# audio_spectrum.net
KiCad netlist of a schematic drawn in EAGLE
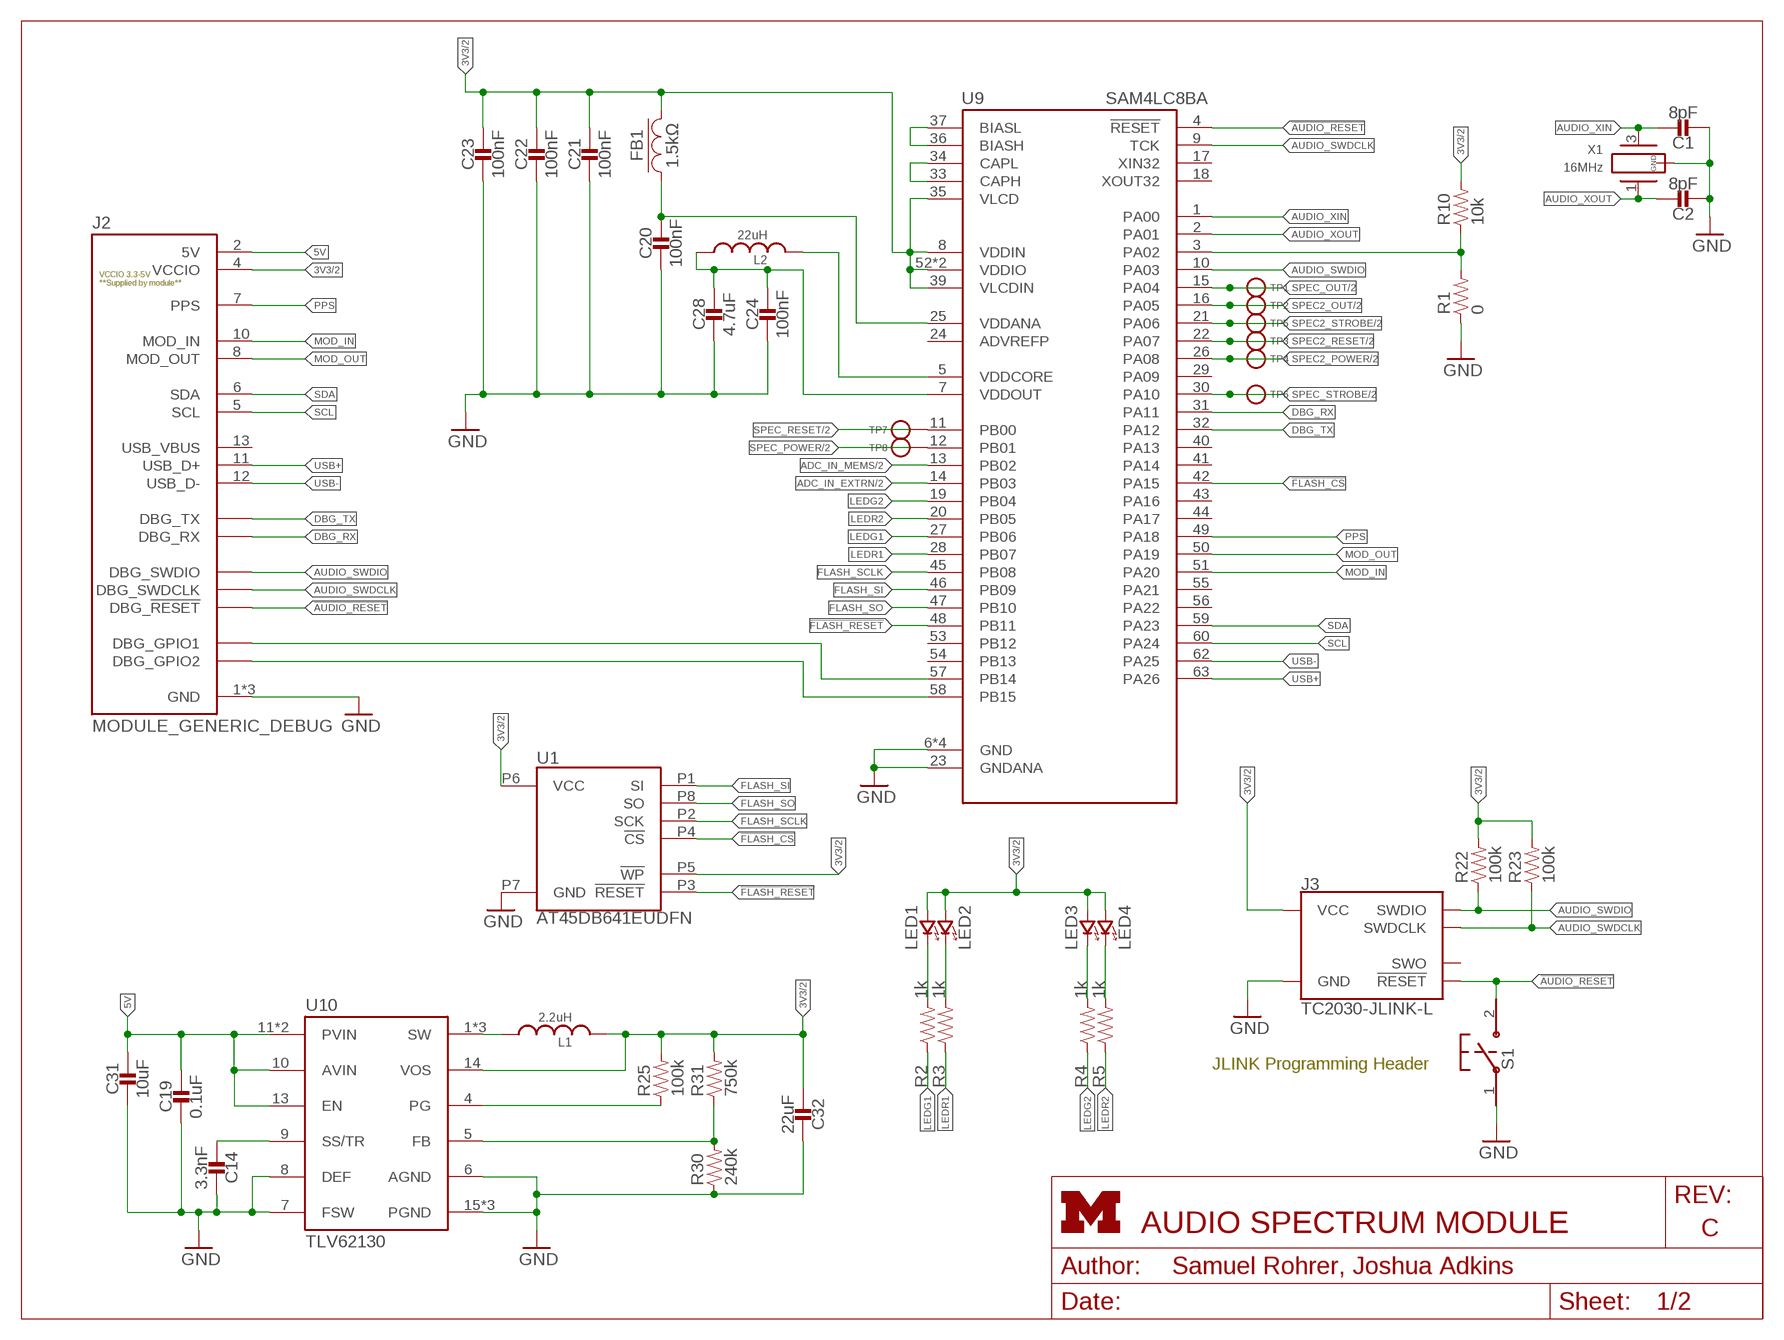
[diagram p0: schematic, sheet 1]
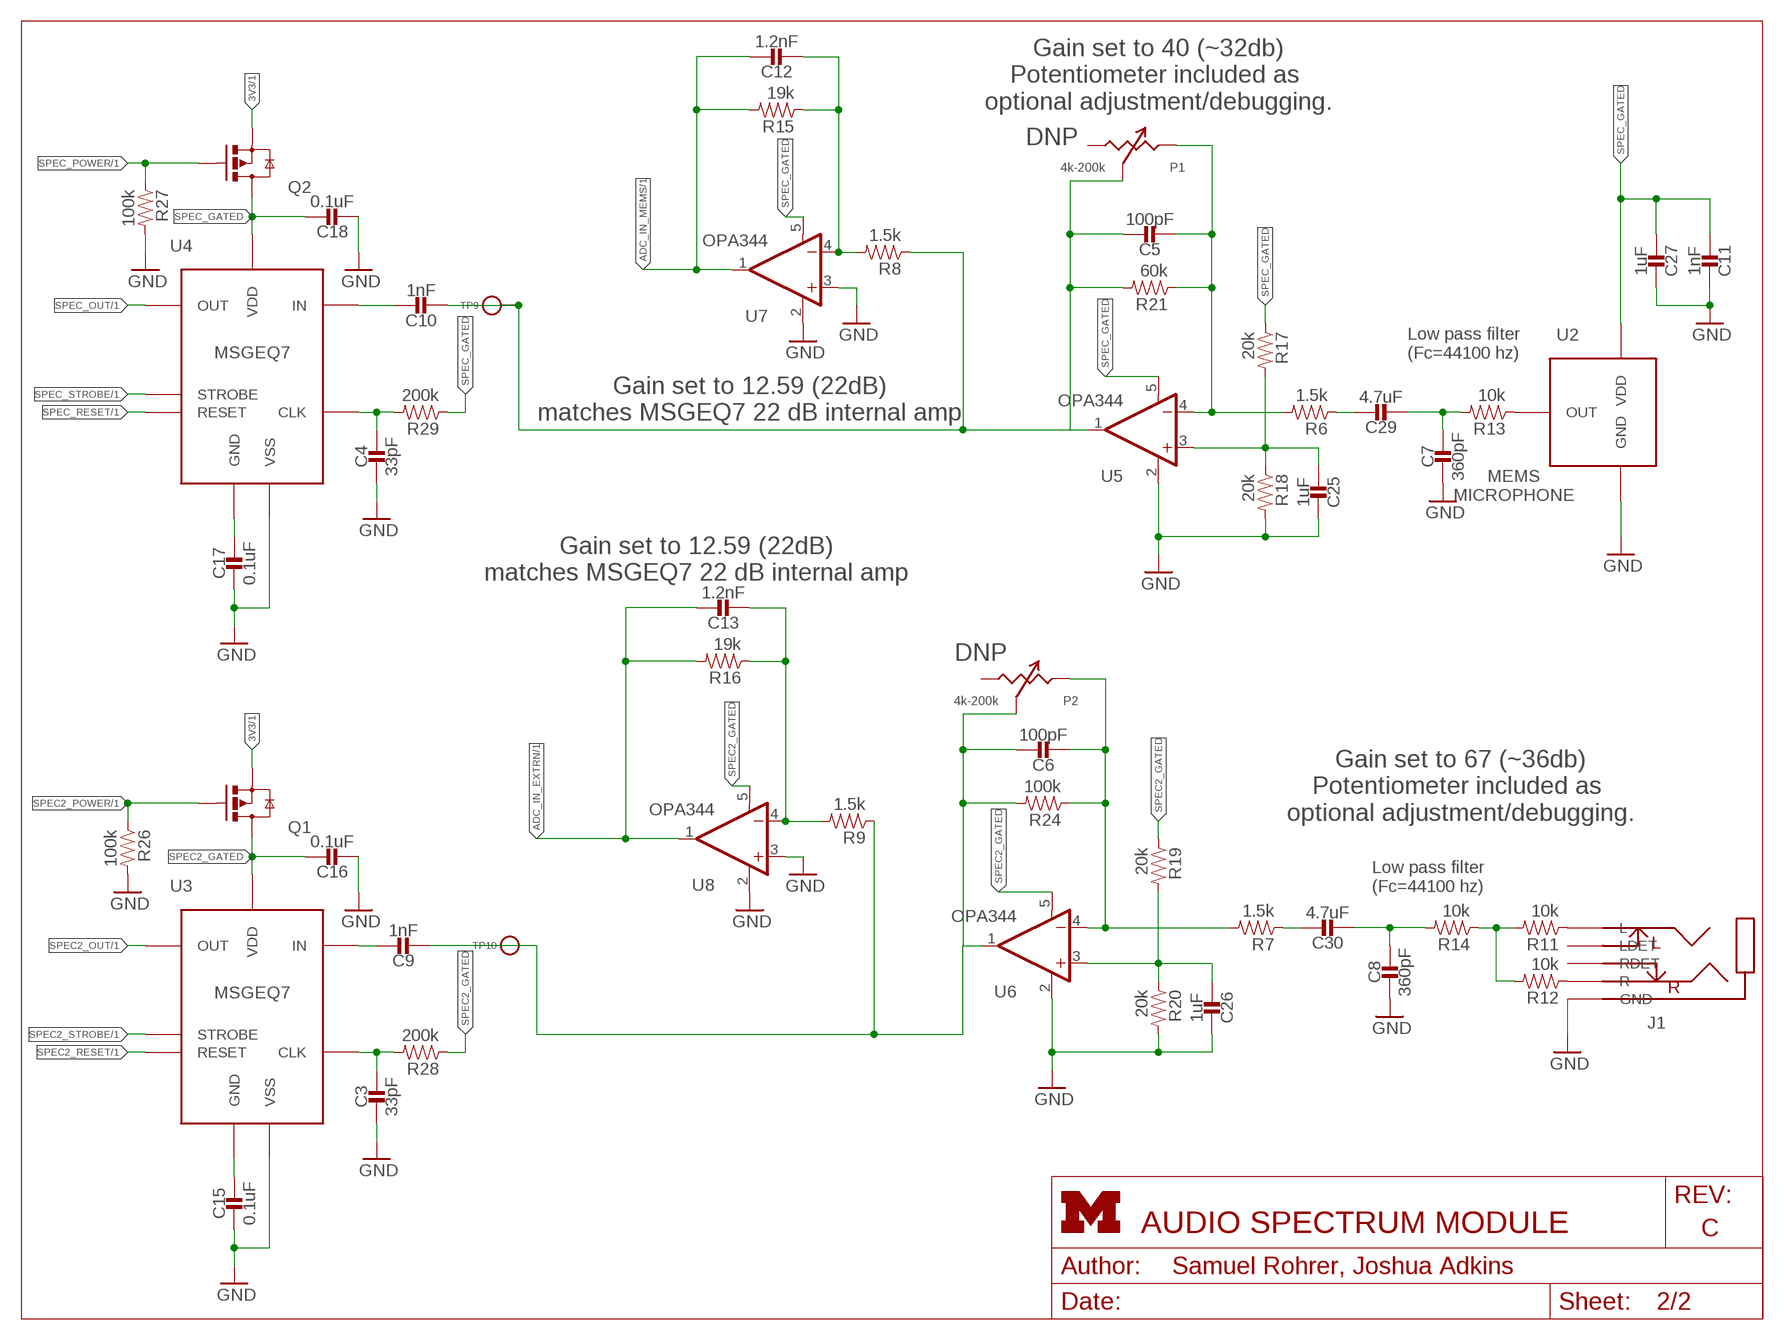
[diagram p1: schematic, sheet 2]

(export (version "E")
  (design (tool "Eeschema 10.0.6"))
  (components
    (comp (ref "C1")
      (value "8pF")
      (footprint "eagle-import:0603_CAP")
      (libsource (lib "eagle-import") (part "CAPACITOR0603_CAP"))
    )
    (comp (ref "C2")
      (value "8pF")
      (footprint "eagle-import:0603_CAP")
      (libsource (lib "eagle-import") (part "CAPACITOR0603_CAP"))
    )
    (comp (ref "C14")
      (value "3.3nF")
      (footprint "eagle-import:0603_CAP")
      (libsource (lib "eagle-import") (part "CAPACITOR0603_CAP"))
    )
    (comp (ref "C19")
      (value "0.1uF")
      (footprint "eagle-import:0603_CAP")
      (libsource (lib "eagle-import") (part "CAPACITOR0603_CAP"))
    )
    (comp (ref "C20")
      (value "100nF")
      (footprint "eagle-import:0603_CAP")
      (libsource (lib "eagle-import") (part "CAPACITOR0603_CAP"))
    )
    (comp (ref "C21")
      (value "100nF")
      (footprint "eagle-import:0603_CAP")
      (libsource (lib "eagle-import") (part "CAPACITOR0603_CAP"))
    )
    (comp (ref "C22")
      (value "100nF")
      (footprint "eagle-import:0603_CAP")
      (libsource (lib "eagle-import") (part "CAPACITOR0603_CAP"))
    )
    (comp (ref "C23")
      (value "100nF")
      (footprint "eagle-import:0603_CAP")
      (libsource (lib "eagle-import") (part "CAPACITOR0603_CAP"))
    )
    (comp (ref "C24")
      (value "100nF")
      (footprint "eagle-import:0402_CAP")
      (libsource (lib "eagle-import") (part "CAPACITOR0402_CAP"))
    )
    (comp (ref "C28")
      (value "4.7uF")
      (footprint "eagle-import:0402_CAP")
      (libsource (lib "eagle-import") (part "CAPACITOR0402_CAP"))
    )
    (comp (ref "C31")
      (value "10uF")
      (footprint "eagle-import:0603_CAP")
      (libsource (lib "eagle-import") (part "CAPACITOR0603_CAP"))
    )
    (comp (ref "C32")
      (value "22uF")
      (footprint "eagle-import:0603_CAP")
      (libsource (lib "eagle-import") (part "CAPACITOR0603_CAP"))
    )
    (comp (ref "FB1")
      (value "1.5kΩ")
      (footprint "eagle-import:0603_CAP")
      (libsource (lib "eagle-import") (part "FERRITE_BEAD0603"))
    )
    (comp (ref "J2")
      (value "MODULE_GENERIC_DEBUG")
      (footprint "eagle-import:MODULE_GENERIC_DEBUG")
      (libsource (lib "eagle-import") (part "MODULE_GENERIC_DEBUG"))
    )
    (comp (ref "J3")
      (value "TC2030-JLINK-L")
      (footprint "eagle-import:TC2030-IDC")
      (libsource (lib "eagle-import") (part "TC2030-JLINK-L"))
    )
    (comp (ref "L1")
      (value "2.2uH")
      (footprint "eagle-import:IHL-1212BZ-11")
      (libsource (lib "eagle-import") (part "INDUCTORIHL"))
    )
    (comp (ref "L2")
      (value "22uH")
      (footprint "eagle-import:1212")
      (libsource (lib "eagle-import") (part "LHQ3NP"))
    )
    (comp (ref "LED1")
      (value "LED0603")
      (footprint "eagle-import:LED-0603")
      (libsource (lib "eagle-import") (part "LED0603"))
    )
    (comp (ref "LED2")
      (value "LED0603")
      (footprint "eagle-import:LED-0603")
      (libsource (lib "eagle-import") (part "LED0603"))
    )
    (comp (ref "LED3")
      (value "LED0603")
      (footprint "eagle-import:LED-0603")
      (libsource (lib "eagle-import") (part "LED0603"))
    )
    (comp (ref "LED4")
      (value "LED0603")
      (footprint "eagle-import:LED-0603")
      (libsource (lib "eagle-import") (part "LED0603"))
    )
    (comp (ref "R1")
      (value "0")
      (footprint "eagle-import:0603-RES")
      (libsource (lib "eagle-import") (part "RESISTOR0603_RES"))
    )
    (comp (ref "R2")
      (value "1k")
      (footprint "eagle-import:0603-RES")
      (libsource (lib "eagle-import") (part "RESISTOR0603_RES"))
    )
    (comp (ref "R3")
      (value "1k")
      (footprint "eagle-import:0603-RES")
      (libsource (lib "eagle-import") (part "RESISTOR0603_RES"))
    )
    (comp (ref "R4")
      (value "1k")
      (footprint "eagle-import:0603-RES")
      (libsource (lib "eagle-import") (part "RESISTOR0603_RES"))
    )
    (comp (ref "R5")
      (value "1k")
      (footprint "eagle-import:0603-RES")
      (libsource (lib "eagle-import") (part "RESISTOR0603_RES"))
    )
    (comp (ref "R10")
      (value "10k")
      (footprint "eagle-import:0603-RES")
      (libsource (lib "eagle-import") (part "RESISTOR0603_RES"))
    )
    (comp (ref "R22")
      (value "100k")
      (footprint "eagle-import:0603-RES")
      (libsource (lib "eagle-import") (part "RESISTOR0603_RES"))
    )
    (comp (ref "R23")
      (value "100k")
      (footprint "eagle-import:0603-RES")
      (libsource (lib "eagle-import") (part "RESISTOR0603_RES"))
    )
    (comp (ref "R25")
      (value "100k")
      (footprint "eagle-import:0603-RES")
      (libsource (lib "eagle-import") (part "RESISTOR0603_RES"))
    )
    (comp (ref "R30")
      (value "240k")
      (footprint "eagle-import:0603-RES")
      (libsource (lib "eagle-import") (part "RESISTOR0603_RES"))
    )
    (comp (ref "R31")
      (value "750k")
      (footprint "eagle-import:0603-RES")
      (libsource (lib "eagle-import") (part "RESISTOR0603_RES"))
    )
    (comp (ref "S1")
      (value "B3U-1000P")
      (footprint "eagle-import:B3U-1000P")
      (libsource (lib "eagle-import") (part "B3U-1000P"))
    )
    (comp (ref "TP1")
      (value "TEST_POINT_0.040IN")
      (footprint "eagle-import:TESTPOINT_0.040IN")
      (libsource (lib "eagle-import") (part "TEST_POINT_0.040IN"))
    )
    (comp (ref "TP2")
      (value "TEST_POINT_0.040IN")
      (footprint "eagle-import:TESTPOINT_0.040IN")
      (libsource (lib "eagle-import") (part "TEST_POINT_0.040IN"))
    )
    (comp (ref "TP3")
      (value "TEST_POINT_0.040IN")
      (footprint "eagle-import:TESTPOINT_0.040IN")
      (libsource (lib "eagle-import") (part "TEST_POINT_0.040IN"))
    )
    (comp (ref "TP4")
      (value "TEST_POINT_0.040IN")
      (footprint "eagle-import:TESTPOINT_0.040IN")
      (libsource (lib "eagle-import") (part "TEST_POINT_0.040IN"))
    )
    (comp (ref "TP5")
      (value "TEST_POINT_0.040IN")
      (footprint "eagle-import:TESTPOINT_0.040IN")
      (libsource (lib "eagle-import") (part "TEST_POINT_0.040IN"))
    )
    (comp (ref "TP6")
      (value "TEST_POINT_0.040IN")
      (footprint "eagle-import:TESTPOINT_0.040IN")
      (libsource (lib "eagle-import") (part "TEST_POINT_0.040IN"))
    )
    (comp (ref "TP7")
      (value "TEST_POINT_0.040IN")
      (footprint "eagle-import:TESTPOINT_0.040IN")
      (libsource (lib "eagle-import") (part "TEST_POINT_0.040IN"))
    )
    (comp (ref "TP8")
      (value "TEST_POINT_0.040IN")
      (footprint "eagle-import:TESTPOINT_0.040IN")
      (libsource (lib "eagle-import") (part "TEST_POINT_0.040IN"))
    )
    (comp (ref "U1")
      (value "AT45DB641EUDFN")
      (footprint "eagle-import:UDFN-8-5MMX6MM")
      (libsource (lib "eagle-import") (part "AT45DB641EUDFN"))
    )
    (comp (ref "U9")
      (value "SAM4LC8BA")
      (footprint "eagle-import:QFN-64-9MM")
      (libsource (lib "eagle-import") (part "SAM4LC8BA"))
    )
    (comp (ref "U10")
      (value "TLV62130")
      (footprint "eagle-import:TQFN-16_3MM")
      (libsource (lib "eagle-import") (part "TLV62130"))
    )
    (comp (ref "X1")
      (value "16MHz")
      (footprint "eagle-import:FHXXX")
      (libsource (lib "eagle-import") (part "FH1600015"))
    )
    (comp (ref "C3")
      (value "33pF")
      (footprint "eagle-import:0603_CAP")
      (libsource (lib "eagle-import") (part "CAPACITOR0603_CAP"))
    )
    (comp (ref "C4")
      (value "33pF")
      (footprint "eagle-import:0603_CAP")
      (libsource (lib "eagle-import") (part "CAPACITOR0603_CAP"))
    )
    (comp (ref "C5")
      (value "100pF")
      (footprint "eagle-import:0603_CAP")
      (libsource (lib "eagle-import") (part "CAPACITOR0603_CAP"))
    )
    (comp (ref "C6")
      (value "100pF")
      (footprint "eagle-import:0603_CAP")
      (libsource (lib "eagle-import") (part "CAPACITOR0603_CAP"))
    )
    (comp (ref "C7")
      (value "360pF")
      (footprint "eagle-import:0603_CAP")
      (libsource (lib "eagle-import") (part "CAPACITOR0603_CAP"))
    )
    (comp (ref "C8")
      (value "360pF")
      (footprint "eagle-import:0603_CAP")
      (libsource (lib "eagle-import") (part "CAPACITOR0603_CAP"))
    )
    (comp (ref "C9")
      (value "1nF")
      (footprint "eagle-import:0603_CAP")
      (libsource (lib "eagle-import") (part "CAPACITOR0603_CAP"))
    )
    (comp (ref "C10")
      (value "1nF")
      (footprint "eagle-import:0603_CAP")
      (libsource (lib "eagle-import") (part "CAPACITOR0603_CAP"))
    )
    (comp (ref "C11")
      (value "1nF")
      (footprint "eagle-import:0603_CAP")
      (libsource (lib "eagle-import") (part "CAPACITOR0603_CAP"))
    )
    (comp (ref "C12")
      (value "1.2nF")
      (footprint "eagle-import:0603_CAP")
      (libsource (lib "eagle-import") (part "CAPACITOR0603_CAP"))
    )
    (comp (ref "C13")
      (value "1.2nF")
      (footprint "eagle-import:0603_CAP")
      (libsource (lib "eagle-import") (part "CAPACITOR0603_CAP"))
    )
    (comp (ref "C15")
      (value "0.1uF")
      (footprint "eagle-import:0603_CAP")
      (libsource (lib "eagle-import") (part "CAPACITOR0603_CAP"))
    )
    (comp (ref "C16")
      (value "0.1uF")
      (footprint "eagle-import:0603_CAP")
      (libsource (lib "eagle-import") (part "CAPACITOR0603_CAP"))
    )
    (comp (ref "C17")
      (value "0.1uF")
      (footprint "eagle-import:0603_CAP")
      (libsource (lib "eagle-import") (part "CAPACITOR0603_CAP"))
    )
    (comp (ref "C18")
      (value "0.1uF")
      (footprint "eagle-import:0603_CAP")
      (libsource (lib "eagle-import") (part "CAPACITOR0603_CAP"))
    )
    (comp (ref "C25")
      (value "1uF")
      (footprint "eagle-import:0603_CAP")
      (libsource (lib "eagle-import") (part "CAPACITOR0603_CAP"))
    )
    (comp (ref "C26")
      (value "1uF")
      (footprint "eagle-import:0603_CAP")
      (libsource (lib "eagle-import") (part "CAPACITOR0603_CAP"))
    )
    (comp (ref "C27")
      (value "1uF")
      (footprint "eagle-import:0603_CAP")
      (libsource (lib "eagle-import") (part "CAPACITOR0603_CAP"))
    )
    (comp (ref "C29")
      (value "4.7uF")
      (footprint "eagle-import:0603_CAP")
      (libsource (lib "eagle-import") (part "CAPACITOR0603_CAP"))
    )
    (comp (ref "C30")
      (value "4.7uF")
      (footprint "eagle-import:0603_CAP")
      (libsource (lib "eagle-import") (part "CAPACITOR0603_CAP"))
    )
    (comp (ref "J1")
      (value "AUDIO-JACK-VERTICAL")
      (footprint "eagle-import:AUDIO-JACK-VERTICAL")
      (libsource (lib "eagle-import") (part "AUDIO-JACK-VERTICAL"))
    )
    (comp (ref "P1")
      (value "4k-200k")
      (footprint "eagle-import:TC33X-2")
      (libsource (lib "eagle-import") (part "POTTC33X"))
    )
    (comp (ref "P2")
      (value "4k-200k")
      (footprint "eagle-import:TC33X-2")
      (libsource (lib "eagle-import") (part "POTTC33X"))
    )
    (comp (ref "Q1")
      (value "NX3008PBK")
      (footprint "eagle-import:SOT23-3")
      (libsource (lib "eagle-import") (part "NX3008PBK"))
    )
    (comp (ref "Q2")
      (value "NX3008PBK")
      (footprint "eagle-import:SOT23-3")
      (libsource (lib "eagle-import") (part "NX3008PBK"))
    )
    (comp (ref "R6")
      (value "1.5k")
      (footprint "eagle-import:0603-RES")
      (libsource (lib "eagle-import") (part "RESISTOR0603_RES"))
    )
    (comp (ref "R7")
      (value "1.5k")
      (footprint "eagle-import:0603-RES")
      (libsource (lib "eagle-import") (part "RESISTOR0603_RES"))
    )
    (comp (ref "R8")
      (value "1.5k")
      (footprint "eagle-import:0603-RES")
      (libsource (lib "eagle-import") (part "RESISTOR0603_RES"))
    )
    (comp (ref "R9")
      (value "1.5k")
      (footprint "eagle-import:0603-RES")
      (libsource (lib "eagle-import") (part "RESISTOR0603_RES"))
    )
    (comp (ref "R11")
      (value "10k")
      (footprint "eagle-import:0603-RES")
      (libsource (lib "eagle-import") (part "RESISTOR0603_RES"))
    )
    (comp (ref "R12")
      (value "10k")
      (footprint "eagle-import:0603-RES")
      (libsource (lib "eagle-import") (part "RESISTOR0603_RES"))
    )
    (comp (ref "R13")
      (value "10k")
      (footprint "eagle-import:0603-RES")
      (libsource (lib "eagle-import") (part "RESISTOR0603_RES"))
    )
    (comp (ref "R14")
      (value "10k")
      (footprint "eagle-import:0603-RES")
      (libsource (lib "eagle-import") (part "RESISTOR0603_RES"))
    )
    (comp (ref "R15")
      (value "19k")
      (footprint "eagle-import:0603-RES")
      (libsource (lib "eagle-import") (part "RESISTOR0603_RES"))
    )
    (comp (ref "R16")
      (value "19k")
      (footprint "eagle-import:0603-RES")
      (libsource (lib "eagle-import") (part "RESISTOR0603_RES"))
    )
    (comp (ref "R17")
      (value "20k")
      (footprint "eagle-import:0603-RES")
      (libsource (lib "eagle-import") (part "RESISTOR0603_RES"))
    )
    (comp (ref "R18")
      (value "20k")
      (footprint "eagle-import:0603-RES")
      (libsource (lib "eagle-import") (part "RESISTOR0603_RES"))
    )
    (comp (ref "R19")
      (value "20k")
      (footprint "eagle-import:0603-RES")
      (libsource (lib "eagle-import") (part "RESISTOR0603_RES"))
    )
    (comp (ref "R20")
      (value "20k")
      (footprint "eagle-import:0603-RES")
      (libsource (lib "eagle-import") (part "RESISTOR0603_RES"))
    )
    (comp (ref "R21")
      (value "60k")
      (footprint "eagle-import:0603-RES")
      (libsource (lib "eagle-import") (part "RESISTOR0603_RES"))
    )
    (comp (ref "R24")
      (value "100k")
      (footprint "eagle-import:0603-RES")
      (libsource (lib "eagle-import") (part "RESISTOR0603_RES"))
    )
    (comp (ref "R26")
      (value "100k")
      (footprint "eagle-import:0603-RES")
      (libsource (lib "eagle-import") (part "RESISTOR0603_RES"))
    )
    (comp (ref "R27")
      (value "100k")
      (footprint "eagle-import:0603-RES")
      (libsource (lib "eagle-import") (part "RESISTOR0603_RES"))
    )
    (comp (ref "R28")
      (value "200k")
      (footprint "eagle-import:0603-RES")
      (libsource (lib "eagle-import") (part "RESISTOR0603_RES"))
    )
    (comp (ref "R29")
      (value "200k")
      (footprint "eagle-import:0603-RES")
      (libsource (lib "eagle-import") (part "RESISTOR0603_RES"))
    )
    (comp (ref "TP9")
      (value "TEST_POINT_0.040IN")
      (footprint "eagle-import:TESTPOINT_0.040IN")
      (libsource (lib "eagle-import") (part "TEST_POINT_0.040IN"))
    )
    (comp (ref "TP10")
      (value "TEST_POINT_0.040IN")
      (footprint "eagle-import:TESTPOINT_0.040IN")
      (libsource (lib "eagle-import") (part "TEST_POINT_0.040IN"))
    )
    (comp (ref "U2")
      (value "MP23AB02B")
      (footprint "eagle-import:MP23AB02B")
      (libsource (lib "eagle-import") (part "MP23AB02B"))
    )
    (comp (ref "U3")
      (value "MSGEQ7")
      (footprint "eagle-import:DIP-8")
      (libsource (lib "eagle-import") (part "MSGEQ7"))
    )
    (comp (ref "U4")
      (value "MSGEQ7")
      (footprint "eagle-import:DIP-8")
      (libsource (lib "eagle-import") (part "MSGEQ7"))
    )
    (comp (ref "U5")
      (value "OPA344")
      (footprint "eagle-import:SOT23-5")
      (libsource (lib "eagle-import") (part "OPA344"))
    )
    (comp (ref "U6")
      (value "OPA344")
      (footprint "eagle-import:SOT23-5")
      (libsource (lib "eagle-import") (part "OPA344"))
    )
    (comp (ref "U7")
      (value "OPA344")
      (footprint "eagle-import:SOT23-5")
      (libsource (lib "eagle-import") (part "OPA344"))
    )
    (comp (ref "U8")
      (value "OPA344")
      (footprint "eagle-import:SOT23-5")
      (libsource (lib "eagle-import") (part "OPA344"))
    )
  )
  (nets
    (net (code "1") (name "3V3") (class "Default")
      (node (ref "C21") (pin "1") (pinfunction "1_1") (pintype "bidirectional"))
      (node (ref "C22") (pin "1") (pinfunction "1_1") (pintype "bidirectional"))
      (node (ref "C23") (pin "1") (pinfunction "1_1") (pintype "bidirectional"))
      (node (ref "C32") (pin "2") (pinfunction "2_2") (pintype "bidirectional"))
      (node (ref "FB1") (pin "2") (pinfunction "P$2_2") (pintype "bidirectional"))
      (node (ref "J2") (pin "4") (pinfunction "VCCIO_4") (pintype "bidirectional"))
      (node (ref "J3") (pin "1") (pinfunction "VCC_1") (pintype "bidirectional"))
      (node (ref "L1") (pin "P$2") (pinfunction "2_P$2") (pintype "bidirectional"))
      (node (ref "LED1") (pin "A") (pinfunction "ANODE_A") (pintype "bidirectional"))
      (node (ref "LED2") (pin "A") (pinfunction "ANODE_A") (pintype "bidirectional"))
      (node (ref "LED3") (pin "A") (pinfunction "ANODE_A") (pintype "bidirectional"))
      (node (ref "LED4") (pin "A") (pinfunction "ANODE_A") (pintype "bidirectional"))
      (node (ref "Q1") (pin "2") (pinfunction "S_2") (pintype "passive"))
      (node (ref "Q2") (pin "2") (pinfunction "S_2") (pintype "passive"))
      (node (ref "R10") (pin "2") (pinfunction "2_2") (pintype "passive"))
      (node (ref "R22") (pin "2") (pinfunction "2_2") (pintype "passive"))
      (node (ref "R23") (pin "2") (pinfunction "2_2") (pintype "passive"))
      (node (ref "R25") (pin "2") (pinfunction "2_2") (pintype "passive"))
      (node (ref "R31") (pin "2") (pinfunction "2_2") (pintype "passive"))
      (node (ref "U1") (pin "P5") (pinfunction "~{WP}_P5") (pintype "bidirectional"))
      (node (ref "U1") (pin "P6") (pinfunction "VCC_P6") (pintype "bidirectional"))
      (node (ref "U10") (pin "14") (pinfunction "VOS_14") (pintype "bidirectional"))
      (node (ref "U9") (pin "35") (pinfunction "VLCD_35") (pintype "bidirectional"))
      (node (ref "U9") (pin "39") (pinfunction "VLCDIN_39") (pintype "power_in"))
      (node (ref "U9") (pin "52") (pinfunction "VDDIO_52") (pintype "power_in"))
      (node (ref "U9") (pin "61") (pinfunction "VDDIO_61") (pintype "power_in"))
      (node (ref "U9") (pin "8") (pinfunction "VDDIN_8") (pintype "power_in"))
    )
    (net (code "2") (name "5V") (class "Default")
      (node (ref "C19") (pin "1") (pinfunction "1_1") (pintype "bidirectional"))
      (node (ref "C31") (pin "1") (pinfunction "1_1") (pintype "bidirectional"))
      (node (ref "J2") (pin "2") (pinfunction "5V_2") (pintype "bidirectional"))
      (node (ref "U10") (pin "10") (pinfunction "AVIN_10") (pintype "bidirectional"))
      (node (ref "U10") (pin "11") (pinfunction "PVIN_11") (pintype "bidirectional"))
      (node (ref "U10") (pin "12") (pinfunction "PVIN_12") (pintype "bidirectional"))
      (node (ref "U10") (pin "13") (pinfunction "EN_13") (pintype "bidirectional"))
    )
    (net (code "3") (name "ADC_IN_EXTRN") (class "Default")
      (node (ref "C13") (pin "1") (pinfunction "1_1") (pintype "bidirectional"))
      (node (ref "R16") (pin "2") (pinfunction "2_2") (pintype "passive"))
      (node (ref "U8") (pin "1") (pinfunction "OUT_1") (pintype "output"))
      (node (ref "U9") (pin "14") (pinfunction "PB03_14") (pintype "bidirectional"))
    )
    (net (code "4") (name "ADC_IN_MEMS") (class "Default")
      (node (ref "C12") (pin "1") (pinfunction "1_1") (pintype "bidirectional"))
      (node (ref "R15") (pin "2") (pinfunction "2_2") (pintype "passive"))
      (node (ref "U7") (pin "1") (pinfunction "OUT_1") (pintype "output"))
      (node (ref "U9") (pin "13") (pinfunction "PB02_13") (pintype "bidirectional"))
    )
    (net (code "5") (name "AUDIO_SWDCLK") (class "Default")
      (node (ref "J2") (pin "21") (pinfunction "DBG_SWDCLK_21") (pintype "bidirectional"))
      (node (ref "J3") (pin "4") (pinfunction "SWDCLK_4") (pintype "bidirectional"))
      (node (ref "R23") (pin "1") (pinfunction "1_1") (pintype "passive"))
      (node (ref "U9") (pin "9") (pinfunction "TCK_9") (pintype "bidirectional"))
    )
    (net (code "6") (name "AUDIO_SWDIO") (class "Default")
      (node (ref "J2") (pin "22") (pinfunction "DBG_SWDIO_22") (pintype "bidirectional"))
      (node (ref "J3") (pin "2") (pinfunction "SWDIO_2") (pintype "bidirectional"))
      (node (ref "R22") (pin "1") (pinfunction "1_1") (pintype "passive"))
      (node (ref "U9") (pin "10") (pinfunction "PA03_10") (pintype "bidirectional"))
    )
    (net (code "7") (name "AUDIO_XIN") (class "Default")
      (node (ref "C1") (pin "1") (pinfunction "1_1") (pintype "bidirectional"))
      (node (ref "U9") (pin "1") (pinfunction "PA00_1") (pintype "bidirectional"))
      (node (ref "X1") (pin "3") (pinfunction "2_3") (pintype "bidirectional"))
    )
    (net (code "8") (name "AUDIO_XOUT") (class "Default")
      (node (ref "C2") (pin "1") (pinfunction "1_1") (pintype "bidirectional"))
      (node (ref "U9") (pin "2") (pinfunction "PA01_2") (pintype "bidirectional"))
      (node (ref "X1") (pin "1") (pinfunction "1_1") (pintype "bidirectional"))
    )
    (net (code "9") (name "DBG_RX") (class "Default")
      (node (ref "J2") (pin "18") (pinfunction "DBG_RX_18") (pintype "bidirectional"))
      (node (ref "U9") (pin "31") (pinfunction "PA11_31") (pintype "bidirectional"))
    )
    (net (code "10") (name "DBG_TX") (class "Default")
      (node (ref "J2") (pin "17") (pinfunction "DBG_TX_17") (pintype "bidirectional"))
      (node (ref "U9") (pin "32") (pinfunction "PA12_32") (pintype "bidirectional"))
    )
    (net (code "11") (name "FLASH_SCLK") (class "Default")
      (node (ref "U1") (pin "P2") (pinfunction "SCK_P2") (pintype "bidirectional"))
      (node (ref "U9") (pin "45") (pinfunction "PB08_45") (pintype "bidirectional"))
    )
    (net (code "12") (name "FLASH_SI") (class "Default")
      (node (ref "U1") (pin "P1") (pinfunction "SI_P1") (pintype "bidirectional"))
      (node (ref "U9") (pin "46") (pinfunction "PB09_46") (pintype "bidirectional"))
    )
    (net (code "13") (name "FLASH_SO") (class "Default")
      (node (ref "U1") (pin "P8") (pinfunction "SO_P8") (pintype "bidirectional"))
      (node (ref "U9") (pin "47") (pinfunction "PB10_47") (pintype "bidirectional"))
    )
    (net (code "14") (name "GND") (class "Default")
      (node (ref "C1") (pin "2") (pinfunction "2_2") (pintype "bidirectional"))
      (node (ref "C11") (pin "1") (pinfunction "1_1") (pintype "bidirectional"))
      (node (ref "C14") (pin "1") (pinfunction "1_1") (pintype "bidirectional"))
      (node (ref "C15") (pin "2") (pinfunction "2_2") (pintype "bidirectional"))
      (node (ref "C16") (pin "2") (pinfunction "2_2") (pintype "bidirectional"))
      (node (ref "C17") (pin "2") (pinfunction "2_2") (pintype "bidirectional"))
      (node (ref "C18") (pin "2") (pinfunction "2_2") (pintype "bidirectional"))
      (node (ref "C19") (pin "2") (pinfunction "2_2") (pintype "bidirectional"))
      (node (ref "C2") (pin "2") (pinfunction "2_2") (pintype "bidirectional"))
      (node (ref "C20") (pin "2") (pinfunction "2_2") (pintype "bidirectional"))
      (node (ref "C21") (pin "2") (pinfunction "2_2") (pintype "bidirectional"))
      (node (ref "C22") (pin "2") (pinfunction "2_2") (pintype "bidirectional"))
      (node (ref "C23") (pin "2") (pinfunction "2_2") (pintype "bidirectional"))
      (node (ref "C24") (pin "2") (pinfunction "2_2") (pintype "bidirectional"))
      (node (ref "C25") (pin "1") (pinfunction "1_1") (pintype "bidirectional"))
      (node (ref "C26") (pin "1") (pinfunction "1_1") (pintype "bidirectional"))
      (node (ref "C27") (pin "1") (pinfunction "1_1") (pintype "bidirectional"))
      (node (ref "C28") (pin "2") (pinfunction "2_2") (pintype "bidirectional"))
      (node (ref "C3") (pin "2") (pinfunction "2_2") (pintype "bidirectional"))
      (node (ref "C31") (pin "2") (pinfunction "2_2") (pintype "bidirectional"))
      (node (ref "C32") (pin "1") (pinfunction "1_1") (pintype "bidirectional"))
      (node (ref "C4") (pin "2") (pinfunction "2_2") (pintype "bidirectional"))
      (node (ref "C7") (pin "2") (pinfunction "2_2") (pintype "bidirectional"))
      (node (ref "C8") (pin "2") (pinfunction "2_2") (pintype "bidirectional"))
      (node (ref "J1") (pin "5") (pinfunction "GND_5") (pintype "bidirectional"))
      (node (ref "J2") (pin "1") (pinfunction "GND_1") (pintype "bidirectional"))
      (node (ref "J2") (pin "14") (pinfunction "GND_14") (pintype "bidirectional"))
      (node (ref "J2") (pin "15") (pinfunction "GND_15") (pintype "bidirectional"))
      (node (ref "J3") (pin "5") (pinfunction "GND_5") (pintype "bidirectional"))
      (node (ref "R1") (pin "1") (pinfunction "1_1") (pintype "passive"))
      (node (ref "R18") (pin "2") (pinfunction "2_2") (pintype "passive"))
      (node (ref "R20") (pin "2") (pinfunction "2_2") (pintype "passive"))
      (node (ref "R26") (pin "2") (pinfunction "2_2") (pintype "passive"))
      (node (ref "R27") (pin "2") (pinfunction "2_2") (pintype "passive"))
      (node (ref "R30") (pin "1") (pinfunction "1_1") (pintype "passive"))
      (node (ref "S1") (pin "1") (pinfunction "P$1_1") (pintype "passive"))
      (node (ref "U1") (pin "P7") (pinfunction "GND_P7") (pintype "bidirectional"))
      (node (ref "U10") (pin "15") (pinfunction "PGND_15") (pintype "bidirectional"))
      (node (ref "U10") (pin "16") (pinfunction "PGND_16") (pintype "bidirectional"))
      (node (ref "U10") (pin "6") (pinfunction "AGND_6") (pintype "bidirectional"))
      (node (ref "U10") (pin "7") (pinfunction "FSW_7") (pintype "bidirectional"))
      (node (ref "U10") (pin "8") (pinfunction "DEF_8") (pintype "bidirectional"))
      (node (ref "U10") (pin "GND") (pinfunction "PGND_GND") (pintype "bidirectional"))
      (node (ref "U2") (pin "3") (pinfunction "GND_3") (pintype "bidirectional"))
      (node (ref "U3") (pin "2") (pinfunction "VSS_2") (pintype "bidirectional"))
      (node (ref "U4") (pin "2") (pinfunction "VSS_2") (pintype "bidirectional"))
      (node (ref "U5") (pin "2") (pinfunction "V-_2") (pintype "power_in"))
      (node (ref "U6") (pin "2") (pinfunction "V-_2") (pintype "power_in"))
      (node (ref "U7") (pin "2") (pinfunction "V-_2") (pintype "power_in"))
      (node (ref "U7") (pin "3") (pinfunction "+IN_3") (pintype "input"))
      (node (ref "U8") (pin "2") (pinfunction "V-_2") (pintype "power_in"))
      (node (ref "U8") (pin "3") (pinfunction "+IN_3") (pintype "input"))
      (node (ref "U9") (pin "23") (pinfunction "GNDANA_23") (pintype "power_in"))
      (node (ref "U9") (pin "38") (pinfunction "GND_38") (pintype "power_in"))
      (node (ref "U9") (pin "6") (pinfunction "GND_6") (pintype "power_in"))
      (node (ref "U9") (pin "64") (pinfunction "GND_64") (pintype "power_in"))
      (node (ref "U9") (pin "GND") (pinfunction "GND_GND") (pintype "power_in"))
      (node (ref "X1") (pin "2") (pinfunction "GND_2") (pintype "bidirectional"))
      (node (ref "X1") (pin "4") (pinfunction "GND_4") (pintype "bidirectional"))
    )
    (net (code "15") (name "LEDG1") (class "Default")
      (node (ref "R2") (pin "1") (pinfunction "1_1") (pintype "passive"))
      (node (ref "U9") (pin "27") (pinfunction "PB06_27") (pintype "bidirectional"))
    )
    (net (code "16") (name "LEDG2") (class "Default")
      (node (ref "R4") (pin "1") (pinfunction "1_1") (pintype "passive"))
      (node (ref "U9") (pin "19") (pinfunction "PB04_19") (pintype "bidirectional"))
    )
    (net (code "17") (name "LEDR1") (class "Default")
      (node (ref "R3") (pin "1") (pinfunction "1_1") (pintype "passive"))
      (node (ref "U9") (pin "28") (pinfunction "PB07_28") (pintype "bidirectional"))
    )
    (net (code "18") (name "LEDR2") (class "Default")
      (node (ref "R5") (pin "1") (pinfunction "1_1") (pintype "passive"))
      (node (ref "U9") (pin "20") (pinfunction "PB05_20") (pintype "bidirectional"))
    )
    (net (code "19") (name "MOD_IN") (class "Default")
      (node (ref "J2") (pin "10") (pinfunction "MOD_IN_10") (pintype "bidirectional"))
      (node (ref "U9") (pin "51") (pinfunction "PA20_51") (pintype "bidirectional"))
    )
    (net (code "20") (name "MOD_OUT") (class "Default")
      (node (ref "J2") (pin "8") (pinfunction "MOD_OUT_8") (pintype "bidirectional"))
      (node (ref "U9") (pin "50") (pinfunction "PA19_50") (pintype "bidirectional"))
    )
    (net (code "21") (name "Net-(C29-Pad1)") (class "Default")
      (node (ref "C29") (pin "1") (pinfunction "1_1") (pintype "bidirectional"))
      (node (ref "R6") (pin "1") (pinfunction "1_1") (pintype "passive"))
    )
    (net (code "22") (name "Net-(C29-Pad2)") (class "Default")
      (node (ref "C29") (pin "2") (pinfunction "2_2") (pintype "bidirectional"))
      (node (ref "C7") (pin "1") (pinfunction "1_1") (pintype "bidirectional"))
      (node (ref "R13") (pin "2") (pinfunction "2_2") (pintype "passive"))
    )
    (net (code "23") (name "Net-(C30-Pad1)") (class "Default")
      (node (ref "C30") (pin "1") (pinfunction "1_1") (pintype "bidirectional"))
      (node (ref "R7") (pin "1") (pinfunction "1_1") (pintype "passive"))
    )
    (net (code "24") (name "Net-(C30-Pad2)") (class "Default")
      (node (ref "C30") (pin "2") (pinfunction "2_2") (pintype "bidirectional"))
      (node (ref "C8") (pin "1") (pinfunction "1_1") (pintype "bidirectional"))
      (node (ref "R14") (pin "2") (pinfunction "2_2") (pintype "passive"))
    )
    (net (code "25") (name "Net-(FB1-P$1)") (class "Default")
      (node (ref "C20") (pin "1") (pinfunction "1_1") (pintype "bidirectional"))
      (node (ref "FB1") (pin "1") (pinfunction "P$1_1") (pintype "bidirectional"))
      (node (ref "U9") (pin "25") (pinfunction "VDDANA_25") (pintype "power_in"))
    )
    (net (code "26") (name "Net-(J1-L)") (class "Default")
      (node (ref "J1") (pin "4") (pinfunction "L_4") (pintype "bidirectional"))
      (node (ref "R11") (pin "1") (pinfunction "1_1") (pintype "passive"))
    )
    (net (code "27") (name "Net-(J1-R)") (class "Default")
      (node (ref "J1") (pin "1") (pinfunction "R_1") (pintype "bidirectional"))
      (node (ref "R12") (pin "1") (pinfunction "1_1") (pintype "passive"))
    )
    (net (code "28") (name "Net-(J2-DBG_GPIO1)") (class "Default")
      (node (ref "J2") (pin "16") (pinfunction "DBG_GPIO1_16") (pintype "bidirectional"))
      (node (ref "U9") (pin "57") (pinfunction "PB14_57") (pintype "bidirectional"))
    )
    (net (code "29") (name "Net-(J2-DBG_GPIO2)") (class "Default")
      (node (ref "J2") (pin "19") (pinfunction "DBG_GPIO2_19") (pintype "bidirectional"))
      (node (ref "U9") (pin "58") (pinfunction "PB15_58") (pintype "bidirectional"))
    )
    (net (code "30") (name "Net-(L1-1)") (class "Default")
      (node (ref "L1") (pin "P$1") (pinfunction "1_P$1") (pintype "bidirectional"))
      (node (ref "U10") (pin "1") (pinfunction "SW_1") (pintype "bidirectional"))
      (node (ref "U10") (pin "2") (pinfunction "SW_2") (pintype "bidirectional"))
      (node (ref "U10") (pin "3") (pinfunction "SW_3") (pintype "bidirectional"))
    )
    (net (code "31") (name "Net-(L2-1)") (class "Default")
      (node (ref "C24") (pin "1") (pinfunction "1_1") (pintype "bidirectional"))
      (node (ref "C28") (pin "1") (pinfunction "1_1") (pintype "bidirectional"))
      (node (ref "L2") (pin "P$1") (pinfunction "1_P$1") (pintype "bidirectional"))
      (node (ref "U9") (pin "7") (pinfunction "VDDOUT_7") (pintype "power_in"))
    )
    (net (code "32") (name "Net-(L2-2)") (class "Default")
      (node (ref "L2") (pin "P$2") (pinfunction "2_P$2") (pintype "bidirectional"))
      (node (ref "U9") (pin "5") (pinfunction "VDDCORE_5") (pintype "power_in"))
    )
    (net (code "33") (name "Net-(LED1-CATHODE)") (class "Default")
      (node (ref "LED1") (pin "C") (pinfunction "CATHODE_C") (pintype "bidirectional"))
      (node (ref "R2") (pin "2") (pinfunction "2_2") (pintype "passive"))
    )
    (net (code "34") (name "Net-(LED2-CATHODE)") (class "Default")
      (node (ref "LED2") (pin "C") (pinfunction "CATHODE_C") (pintype "bidirectional"))
      (node (ref "R3") (pin "2") (pinfunction "2_2") (pintype "passive"))
    )
    (net (code "35") (name "Net-(LED3-CATHODE)") (class "Default")
      (node (ref "LED3") (pin "C") (pinfunction "CATHODE_C") (pintype "bidirectional"))
      (node (ref "R4") (pin "2") (pinfunction "2_2") (pintype "passive"))
    )
    (net (code "36") (name "Net-(LED4-CATHODE)") (class "Default")
      (node (ref "LED4") (pin "C") (pinfunction "CATHODE_C") (pintype "bidirectional"))
      (node (ref "R5") (pin "2") (pinfunction "2_2") (pintype "passive"))
    )
    (net (code "37") (name "Net-(P1-CW)") (class "Default")
      (node (ref "C5") (pin "2") (pinfunction "2_2") (pintype "bidirectional"))
      (node (ref "P1") (pin "2") (pinfunction "CW_2") (pintype "bidirectional"))
      (node (ref "R21") (pin "1") (pinfunction "1_1") (pintype "passive"))
      (node (ref "R6") (pin "2") (pinfunction "2_2") (pintype "passive"))
      (node (ref "U5") (pin "4") (pinfunction "-IN_4") (pintype "input"))
    )
    (net (code "38") (name "Net-(P1-W)") (class "Default")
      (node (ref "C10") (pin "2") (pinfunction "2_2") (pintype "bidirectional"))
      (node (ref "C5") (pin "1") (pinfunction "1_1") (pintype "bidirectional"))
      (node (ref "P1") (pin "3") (pinfunction "W_3") (pintype "bidirectional"))
      (node (ref "R21") (pin "2") (pinfunction "2_2") (pintype "passive"))
      (node (ref "R8") (pin "1") (pinfunction "1_1") (pintype "passive"))
      (node (ref "TP9") (pin "TESTPOINT") (pinfunction "TESTPOINT_TESTPOINT") (pintype "bidirectional"))
      (node (ref "U5") (pin "1") (pinfunction "OUT_1") (pintype "output"))
    )
    (net (code "39") (name "Net-(P2-CW)") (class "Default")
      (node (ref "C6") (pin "2") (pinfunction "2_2") (pintype "bidirectional"))
      (node (ref "P2") (pin "2") (pinfunction "CW_2") (pintype "bidirectional"))
      (node (ref "R24") (pin "1") (pinfunction "1_1") (pintype "passive"))
      (node (ref "R7") (pin "2") (pinfunction "2_2") (pintype "passive"))
      (node (ref "U6") (pin "4") (pinfunction "-IN_4") (pintype "input"))
    )
    (net (code "40") (name "Net-(P2-W)") (class "Default")
      (node (ref "C6") (pin "1") (pinfunction "1_1") (pintype "bidirectional"))
      (node (ref "C9") (pin "2") (pinfunction "2_2") (pintype "bidirectional"))
      (node (ref "P2") (pin "3") (pinfunction "W_3") (pintype "bidirectional"))
      (node (ref "R24") (pin "2") (pinfunction "2_2") (pintype "passive"))
      (node (ref "R9") (pin "1") (pinfunction "1_1") (pintype "passive"))
      (node (ref "TP10") (pin "TESTPOINT") (pinfunction "TESTPOINT_TESTPOINT") (pintype "bidirectional"))
      (node (ref "U6") (pin "1") (pinfunction "OUT_1") (pintype "output"))
    )
    (net (code "41") (name "Net-(R11-Pad2)") (class "Default")
      (node (ref "R11") (pin "2") (pinfunction "2_2") (pintype "passive"))
      (node (ref "R12") (pin "2") (pinfunction "2_2") (pintype "passive"))
      (node (ref "R14") (pin "1") (pinfunction "1_1") (pintype "passive"))
    )
    (net (code "42") (name "Net-(U2-OUT)") (class "Default")
      (node (ref "R13") (pin "1") (pinfunction "1_1") (pintype "passive"))
      (node (ref "U2") (pin "1") (pinfunction "OUT_1") (pintype "bidirectional"))
    )
    (net (code "43") (name "Net-(U3-CLK)") (class "Default")
      (node (ref "C3") (pin "1") (pinfunction "1_1") (pintype "bidirectional"))
      (node (ref "R28") (pin "2") (pinfunction "2_2") (pintype "passive"))
      (node (ref "U3") (pin "8") (pinfunction "CLK_8") (pintype "bidirectional"))
    )
    (net (code "44") (name "Net-(U3-GND)") (class "Default")
      (node (ref "C15") (pin "1") (pinfunction "1_1") (pintype "bidirectional"))
      (node (ref "U3") (pin "6") (pinfunction "GND_6") (pintype "bidirectional"))
    )
    (net (code "45") (name "Net-(U3-IN)") (class "Default")
      (node (ref "C9") (pin "1") (pinfunction "1_1") (pintype "bidirectional"))
      (node (ref "U3") (pin "5") (pinfunction "IN_5") (pintype "bidirectional"))
    )
    (net (code "46") (name "Net-(U4-CLK)") (class "Default")
      (node (ref "C4") (pin "1") (pinfunction "1_1") (pintype "bidirectional"))
      (node (ref "R29") (pin "2") (pinfunction "2_2") (pintype "passive"))
      (node (ref "U4") (pin "8") (pinfunction "CLK_8") (pintype "bidirectional"))
    )
    (net (code "47") (name "Net-(U4-GND)") (class "Default")
      (node (ref "C17") (pin "1") (pinfunction "1_1") (pintype "bidirectional"))
      (node (ref "U4") (pin "6") (pinfunction "GND_6") (pintype "bidirectional"))
    )
    (net (code "48") (name "Net-(U4-IN)") (class "Default")
      (node (ref "C10") (pin "1") (pinfunction "1_1") (pintype "bidirectional"))
      (node (ref "U4") (pin "5") (pinfunction "IN_5") (pintype "bidirectional"))
    )
    (net (code "49") (name "Net-(U5-+IN)") (class "Default")
      (node (ref "C25") (pin "2") (pinfunction "2_2") (pintype "bidirectional"))
      (node (ref "R17") (pin "2") (pinfunction "2_2") (pintype "passive"))
      (node (ref "R18") (pin "1") (pinfunction "1_1") (pintype "passive"))
      (node (ref "U5") (pin "3") (pinfunction "+IN_3") (pintype "input"))
    )
    (net (code "50") (name "Net-(U6-+IN)") (class "Default")
      (node (ref "C26") (pin "2") (pinfunction "2_2") (pintype "bidirectional"))
      (node (ref "R19") (pin "2") (pinfunction "2_2") (pintype "passive"))
      (node (ref "R20") (pin "1") (pinfunction "1_1") (pintype "passive"))
      (node (ref "U6") (pin "3") (pinfunction "+IN_3") (pintype "input"))
    )
    (net (code "51") (name "Net-(U7--IN)") (class "Default")
      (node (ref "C12") (pin "2") (pinfunction "2_2") (pintype "bidirectional"))
      (node (ref "R15") (pin "1") (pinfunction "1_1") (pintype "passive"))
      (node (ref "R8") (pin "2") (pinfunction "2_2") (pintype "passive"))
      (node (ref "U7") (pin "4") (pinfunction "-IN_4") (pintype "input"))
    )
    (net (code "52") (name "Net-(U8--IN)") (class "Default")
      (node (ref "C13") (pin "2") (pinfunction "2_2") (pintype "bidirectional"))
      (node (ref "R16") (pin "1") (pinfunction "1_1") (pintype "passive"))
      (node (ref "R9") (pin "2") (pinfunction "2_2") (pintype "passive"))
      (node (ref "U8") (pin "4") (pinfunction "-IN_4") (pintype "input"))
    )
    (net (code "53") (name "Net-(U9-BIASH)") (class "Default")
      (node (ref "U9") (pin "36") (pinfunction "BIASH_36") (pintype "bidirectional"))
      (node (ref "U9") (pin "37") (pinfunction "BIASL_37") (pintype "bidirectional"))
    )
    (net (code "54") (name "Net-(U9-CAPH)") (class "Default")
      (node (ref "U9") (pin "33") (pinfunction "CAPH_33") (pintype "bidirectional"))
      (node (ref "U9") (pin "34") (pinfunction "CAPL_34") (pintype "bidirectional"))
    )
    (net (code "55") (name "Net-(U9-PA02)") (class "Default")
      (node (ref "R1") (pin "2") (pinfunction "2_2") (pintype "passive"))
      (node (ref "R10") (pin "1") (pinfunction "1_1") (pintype "passive"))
      (node (ref "U9") (pin "3") (pinfunction "PA02_3") (pintype "bidirectional"))
    )
    (net (code "56") (name "Net-(U9-PB00)") (class "Default")
      (node (ref "TP7") (pin "TESTPOINT") (pinfunction "TESTPOINT_TESTPOINT") (pintype "bidirectional"))
      (node (ref "U9") (pin "11") (pinfunction "PB00_11") (pintype "bidirectional"))
    )
    (net (code "57") (name "Net-(U9-PB01)") (class "Default")
      (node (ref "TP8") (pin "TESTPOINT") (pinfunction "TESTPOINT_TESTPOINT") (pintype "bidirectional"))
      (node (ref "U9") (pin "12") (pinfunction "PB01_12") (pintype "bidirectional"))
    )
    (net (code "58") (name "Net-(U10-FB)") (class "Default")
      (node (ref "R30") (pin "2") (pinfunction "2_2") (pintype "passive"))
      (node (ref "R31") (pin "1") (pinfunction "1_1") (pintype "passive"))
      (node (ref "U10") (pin "5") (pinfunction "FB_5") (pintype "bidirectional"))
    )
    (net (code "59") (name "Net-(U10-PG)") (class "Default")
      (node (ref "R25") (pin "1") (pinfunction "1_1") (pintype "passive"))
      (node (ref "U10") (pin "4") (pinfunction "PG_4") (pintype "bidirectional"))
    )
    (net (code "60") (name "Net-(U10-SS{slash}TR)") (class "Default")
      (node (ref "C14") (pin "2") (pinfunction "2_2") (pintype "bidirectional"))
      (node (ref "U10") (pin "9") (pinfunction "SS/TR_9") (pintype "bidirectional"))
    )
    (net (code "61") (name "PPS") (class "Default")
      (node (ref "J2") (pin "7") (pinfunction "PPS_7") (pintype "bidirectional"))
      (node (ref "U9") (pin "49") (pinfunction "PA18_49") (pintype "bidirectional"))
    )
    (net (code "62") (name "SCL") (class "Default")
      (node (ref "J2") (pin "5") (pinfunction "SCL_5") (pintype "bidirectional"))
      (node (ref "U9") (pin "60") (pinfunction "PA24_60") (pintype "bidirectional"))
    )
    (net (code "63") (name "SDA") (class "Default")
      (node (ref "J2") (pin "6") (pinfunction "SDA_6") (pintype "bidirectional"))
      (node (ref "U9") (pin "59") (pinfunction "PA23_59") (pintype "bidirectional"))
    )
    (net (code "64") (name "SPEC2_GATED") (class "Default")
      (node (ref "C16") (pin "1") (pinfunction "1_1") (pintype "bidirectional"))
      (node (ref "Q1") (pin "3") (pinfunction "D_3") (pintype "passive"))
      (node (ref "R19") (pin "1") (pinfunction "1_1") (pintype "passive"))
      (node (ref "R28") (pin "1") (pinfunction "1_1") (pintype "passive"))
      (node (ref "U3") (pin "1") (pinfunction "VDD_1") (pintype "bidirectional"))
      (node (ref "U6") (pin "5") (pinfunction "V+_5") (pintype "power_in"))
      (node (ref "U8") (pin "5") (pinfunction "V+_5") (pintype "power_in"))
    )
    (net (code "65") (name "SPEC2_OUT") (class "Default")
      (node (ref "TP2") (pin "TESTPOINT") (pinfunction "TESTPOINT_TESTPOINT") (pintype "bidirectional"))
      (node (ref "U3") (pin "3") (pinfunction "OUT_3") (pintype "bidirectional"))
      (node (ref "U9") (pin "16") (pinfunction "PA05_16") (pintype "bidirectional"))
    )
    (net (code "66") (name "SPEC2_POWER") (class "Default")
      (node (ref "Q1") (pin "1") (pinfunction "G_1") (pintype "passive"))
      (node (ref "R26") (pin "1") (pinfunction "1_1") (pintype "passive"))
      (node (ref "TP4") (pin "TESTPOINT") (pinfunction "TESTPOINT_TESTPOINT") (pintype "bidirectional"))
      (node (ref "U9") (pin "26") (pinfunction "PA08_26") (pintype "bidirectional"))
    )
    (net (code "67") (name "SPEC2_RESET") (class "Default")
      (node (ref "TP3") (pin "TESTPOINT") (pinfunction "TESTPOINT_TESTPOINT") (pintype "bidirectional"))
      (node (ref "U3") (pin "7") (pinfunction "RESET_7") (pintype "bidirectional"))
      (node (ref "U9") (pin "22") (pinfunction "PA07_22") (pintype "bidirectional"))
    )
    (net (code "68") (name "SPEC2_STROBE") (class "Default")
      (node (ref "TP5") (pin "TESTPOINT") (pinfunction "TESTPOINT_TESTPOINT") (pintype "bidirectional"))
      (node (ref "U3") (pin "4") (pinfunction "STROBE_4") (pintype "bidirectional"))
      (node (ref "U9") (pin "21") (pinfunction "PA06_21") (pintype "bidirectional"))
    )
    (net (code "69") (name "SPEC_GATED") (class "Default")
      (node (ref "C11") (pin "2") (pinfunction "2_2") (pintype "bidirectional"))
      (node (ref "C18") (pin "1") (pinfunction "1_1") (pintype "bidirectional"))
      (node (ref "C27") (pin "2") (pinfunction "2_2") (pintype "bidirectional"))
      (node (ref "Q2") (pin "3") (pinfunction "D_3") (pintype "passive"))
      (node (ref "R17") (pin "1") (pinfunction "1_1") (pintype "passive"))
      (node (ref "R29") (pin "1") (pinfunction "1_1") (pintype "passive"))
      (node (ref "U2") (pin "2") (pinfunction "VDD_2") (pintype "bidirectional"))
      (node (ref "U4") (pin "1") (pinfunction "VDD_1") (pintype "bidirectional"))
      (node (ref "U5") (pin "5") (pinfunction "V+_5") (pintype "power_in"))
      (node (ref "U7") (pin "5") (pinfunction "V+_5") (pintype "power_in"))
    )
    (net (code "70") (name "SPEC_OUT") (class "Default")
      (node (ref "TP1") (pin "TESTPOINT") (pinfunction "TESTPOINT_TESTPOINT") (pintype "bidirectional"))
      (node (ref "U4") (pin "3") (pinfunction "OUT_3") (pintype "bidirectional"))
      (node (ref "U9") (pin "15") (pinfunction "PA04_15") (pintype "bidirectional"))
    )
    (net (code "71") (name "SPEC_POWER") (class "Default")
      (node (ref "Q2") (pin "1") (pinfunction "G_1") (pintype "passive"))
      (node (ref "R27") (pin "1") (pinfunction "1_1") (pintype "passive"))
    )
    (net (code "72") (name "SPEC_RESET") (class "Default")
      (node (ref "U4") (pin "7") (pinfunction "RESET_7") (pintype "bidirectional"))
    )
    (net (code "73") (name "SPEC_STROBE") (class "Default")
      (node (ref "TP6") (pin "TESTPOINT") (pinfunction "TESTPOINT_TESTPOINT") (pintype "bidirectional"))
      (node (ref "U4") (pin "4") (pinfunction "STROBE_4") (pintype "bidirectional"))
      (node (ref "U9") (pin "30") (pinfunction "PA10_30") (pintype "bidirectional"))
    )
    (net (code "74") (name "USB+") (class "Default")
      (node (ref "J2") (pin "11") (pinfunction "USB_D+_11") (pintype "bidirectional"))
      (node (ref "U9") (pin "63") (pinfunction "PA26_63") (pintype "bidirectional"))
    )
    (net (code "75") (name "USB-") (class "Default")
      (node (ref "J2") (pin "12") (pinfunction "USB_D-_12") (pintype "bidirectional"))
      (node (ref "U9") (pin "62") (pinfunction "PA25_62") (pintype "bidirectional"))
    )
    (net (code "76") (name "unconnected-(J1-LDET-Pad3)") (class "Default")
      (node (ref "J1") (pin "3") (pinfunction "LDET_3") (pintype "bidirectional"))
    )
    (net (code "77") (name "unconnected-(J1-RDET-Pad2)") (class "Default")
      (node (ref "J1") (pin "2") (pinfunction "RDET_2") (pintype "bidirectional"))
    )
    (net (code "78") (name "unconnected-(J2-USB_VBUS-Pad13)") (class "Default")
      (node (ref "J2") (pin "13") (pinfunction "USB_VBUS_13") (pintype "bidirectional"))
    )
    (net (code "79") (name "unconnected-(J3-SWO-Pad6)") (class "Default")
      (node (ref "J3") (pin "6") (pinfunction "SWO_6") (pintype "bidirectional"))
    )
    (net (code "80") (name "unconnected-(P1-CCW-Pad1)") (class "Default")
      (node (ref "P1") (pin "1") (pinfunction "CCW_1") (pintype "bidirectional"))
    )
    (net (code "81") (name "unconnected-(P2-CCW-Pad1)") (class "Default")
      (node (ref "P2") (pin "1") (pinfunction "CCW_1") (pintype "bidirectional"))
    )
    (net (code "82") (name "unconnected-(U9-ADVREFP-Pad24)") (class "Default")
      (node (ref "U9") (pin "24") (pinfunction "ADVREFP_24") (pintype "bidirectional"))
    )
    (net (code "83") (name "unconnected-(U9-PA09-Pad29)") (class "Default")
      (node (ref "U9") (pin "29") (pinfunction "PA09_29") (pintype "bidirectional"))
    )
    (net (code "84") (name "unconnected-(U9-PA13-Pad40)") (class "Default")
      (node (ref "U9") (pin "40") (pinfunction "PA13_40") (pintype "bidirectional"))
    )
    (net (code "85") (name "unconnected-(U9-PA14-Pad41)") (class "Default")
      (node (ref "U9") (pin "41") (pinfunction "PA14_41") (pintype "bidirectional"))
    )
    (net (code "86") (name "unconnected-(U9-PA16-Pad43)") (class "Default")
      (node (ref "U9") (pin "43") (pinfunction "PA16_43") (pintype "bidirectional"))
    )
    (net (code "87") (name "unconnected-(U9-PA17-Pad44)") (class "Default")
      (node (ref "U9") (pin "44") (pinfunction "PA17_44") (pintype "bidirectional"))
    )
    (net (code "88") (name "unconnected-(U9-PA21-Pad55)") (class "Default")
      (node (ref "U9") (pin "55") (pinfunction "PA21_55") (pintype "bidirectional"))
    )
    (net (code "89") (name "unconnected-(U9-PA22-Pad56)") (class "Default")
      (node (ref "U9") (pin "56") (pinfunction "PA22_56") (pintype "bidirectional"))
    )
    (net (code "90") (name "unconnected-(U9-PB12-Pad53)") (class "Default")
      (node (ref "U9") (pin "53") (pinfunction "PB12_53") (pintype "bidirectional"))
    )
    (net (code "91") (name "unconnected-(U9-PB13-Pad54)") (class "Default")
      (node (ref "U9") (pin "54") (pinfunction "PB13_54") (pintype "bidirectional"))
    )
    (net (code "92") (name "unconnected-(U9-XIN32-Pad17)") (class "Default")
      (node (ref "U9") (pin "17") (pinfunction "XIN32_17") (pintype "bidirectional"))
    )
    (net (code "93") (name "unconnected-(U9-XOUT32-Pad18)") (class "Default")
      (node (ref "U9") (pin "18") (pinfunction "XOUT32_18") (pintype "bidirectional"))
    )
    (net (code "94") (name "~{AUDIO_RESET}") (class "Default")
      (node (ref "J2") (pin "20") (pinfunction "DBG_~{RESET}_20") (pintype "bidirectional"))
      (node (ref "J3") (pin "3") (pinfunction "~{RESET}_3") (pintype "bidirectional"))
      (node (ref "S1") (pin "2") (pinfunction "P$2_2") (pintype "passive"))
      (node (ref "U9") (pin "4") (pinfunction "~{RESET}_4") (pintype "bidirectional"))
    )
    (net (code "95") (name "~{FLASH_CS}") (class "Default")
      (node (ref "U1") (pin "P4") (pinfunction "~{CS}_P4") (pintype "bidirectional"))
      (node (ref "U9") (pin "42") (pinfunction "PA15_42") (pintype "bidirectional"))
    )
    (net (code "96") (name "~{FLASH_RESET}") (class "Default")
      (node (ref "U1") (pin "P3") (pinfunction "~{RESET}_P3") (pintype "bidirectional"))
      (node (ref "U9") (pin "48") (pinfunction "PB11_48") (pintype "bidirectional"))
    )
  )
)
